# PICMX340F512H.net
KiCad netlist of a schematic drawn in Altium Designer
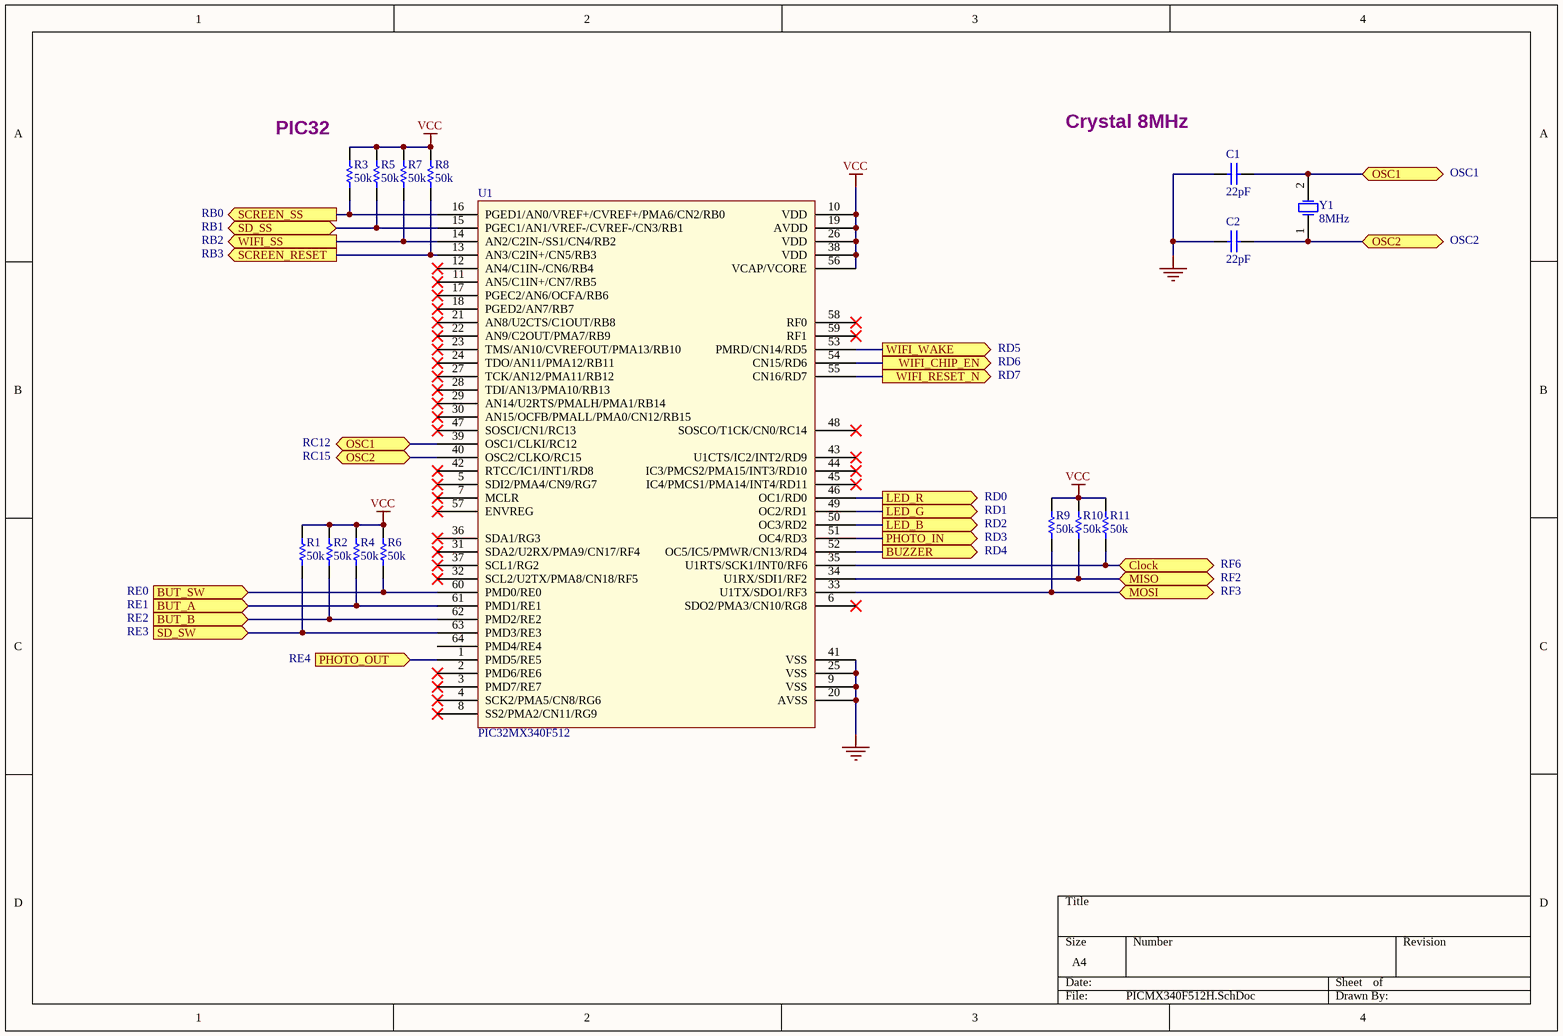
[diagram p0: PICMX340F512H.SchDoc]

(export (version "E")
  (design (tool "Eeschema 10.0.6"))
  (components
    (comp (ref "C1")
      (value "22pF")
      (footprint "CAPC1608X90N")
      (description "Capacitor")
      (libsource (lib "POP_lib") (part "Capacitor"))
    )
    (comp (ref "C2")
      (value "22pF")
      (footprint "CAPC1608X90N")
      (description "Capacitor")
      (libsource (lib "POP_lib") (part "Capacitor"))
    )
    (comp (ref "R1")
      (value "50k")
      (footprint "RESC1608X55N")
      (description "Resistor")
      (fields (field (name "PUBLISHER") "Altium Limited"))
      (libsource (lib "POP_lib") (part "Resistor"))
    )
    (comp (ref "R2")
      (value "50k")
      (footprint "RESC1608X55N")
      (description "Resistor")
      (fields (field (name "PUBLISHER") "Altium Limited"))
      (libsource (lib "POP_lib") (part "Resistor"))
    )
    (comp (ref "R3")
      (value "50k")
      (footprint "RESC1608X55N")
      (description "Resistor")
      (fields (field (name "PUBLISHER") "Altium Limited"))
      (libsource (lib "POP_lib") (part "Resistor"))
    )
    (comp (ref "R4")
      (value "50k")
      (footprint "RESC1608X55N")
      (description "Resistor")
      (fields (field (name "PUBLISHER") "Altium Limited"))
      (libsource (lib "POP_lib") (part "Resistor"))
    )
    (comp (ref "R5")
      (value "50k")
      (footprint "RESC1608X55N")
      (description "Resistor")
      (fields (field (name "PUBLISHER") "Altium Limited"))
      (libsource (lib "POP_lib") (part "Resistor"))
    )
    (comp (ref "R6")
      (value "50k")
      (footprint "RESC1608X55N")
      (description "Resistor")
      (fields (field (name "PUBLISHER") "Altium Limited"))
      (libsource (lib "POP_lib") (part "Resistor"))
    )
    (comp (ref "R7")
      (value "50k")
      (footprint "RESC1608X55N")
      (description "Resistor")
      (fields (field (name "PUBLISHER") "Altium Limited"))
      (libsource (lib "POP_lib") (part "Resistor"))
    )
    (comp (ref "R8")
      (value "50k")
      (footprint "RESC1608X55N")
      (description "Resistor")
      (fields (field (name "PUBLISHER") "Altium Limited"))
      (libsource (lib "POP_lib") (part "Resistor"))
    )
    (comp (ref "R9")
      (value "50k")
      (footprint "RESC1608X55N")
      (description "Resistor")
      (fields (field (name "PUBLISHER") "Altium Limited"))
      (libsource (lib "POP_lib") (part "Resistor"))
    )
    (comp (ref "R10")
      (value "50k")
      (footprint "RESC1608X55N")
      (description "Resistor")
      (fields (field (name "PUBLISHER") "Altium Limited"))
      (libsource (lib "POP_lib") (part "Resistor"))
    )
    (comp (ref "R11")
      (value "50k")
      (footprint "RESC1608X55N")
      (description "Resistor")
      (fields (field (name "PUBLISHER") "Altium Limited"))
      (libsource (lib "POP_lib") (part "Resistor"))
    )
    (comp (ref "U1")
      (value "PIC32MX340F512")
      (description "Protoboard_pic")
      (libsource (lib "POP_lib") (part "PIC32MX340F512H"))
    )
    (comp (ref "Y1")
      (value "8MHz")
      (footprint "XTAL139X50X45")
      (description "Crystal Oscillator")
      (libsource (lib "POP_lib") (part "Crystal"))
    )
  )
  (nets
    (net (code "1") (name "/BUT_A") (class "Default")
      (node (ref "R4") (pin "1") (pinfunction "1_1") (pintype "passive"))
      (node (ref "U1") (pin "61") (pinfunction "PMD1/RE1_61") (pintype "passive"))
    )
    (net (code "2") (name "/BUT_B") (class "Default")
      (node (ref "R2") (pin "1") (pinfunction "1_1") (pintype "passive"))
      (node (ref "U1") (pin "62") (pinfunction "PMD2/RE2_62") (pintype "passive"))
    )
    (net (code "3") (name "/BUT_SW") (class "Default")
      (node (ref "R6") (pin "1") (pinfunction "1_1") (pintype "passive"))
      (node (ref "U1") (pin "60") (pinfunction "PMD0/RE0_60") (pintype "passive"))
    )
    (net (code "4") (name "/BUZZER") (class "Default")
      (node (ref "U1") (pin "52") (pinfunction "OC5/IC5/PMWR/CN13/RD4_52") (pintype "passive"))
    )
    (net (code "5") (name "/Clock") (class "Default")
      (node (ref "R11") (pin "1") (pinfunction "1_1") (pintype "passive"))
      (node (ref "U1") (pin "35") (pinfunction "U1RTS/SCK1/INT0/RF6_35") (pintype "passive"))
    )
    (net (code "6") (name "/LED_B") (class "Default")
      (node (ref "U1") (pin "50") (pinfunction "OC3/RD2_50") (pintype "passive"))
    )
    (net (code "7") (name "/LED_G") (class "Default")
      (node (ref "U1") (pin "49") (pinfunction "OC2/RD1_49") (pintype "passive"))
    )
    (net (code "8") (name "/LED_R") (class "Default")
      (node (ref "U1") (pin "46") (pinfunction "OC1/RD0_46") (pintype "passive"))
    )
    (net (code "9") (name "/MISO") (class "Default")
      (node (ref "R10") (pin "1") (pinfunction "1_1") (pintype "passive"))
      (node (ref "U1") (pin "34") (pinfunction "U1RX/SDI1/RF2_34") (pintype "passive"))
    )
    (net (code "10") (name "/MOSI") (class "Default")
      (node (ref "R9") (pin "1") (pinfunction "1_1") (pintype "passive"))
      (node (ref "U1") (pin "33") (pinfunction "U1TX/SDO1/RF3_33") (pintype "passive"))
    )
    (net (code "11") (name "/OSC1") (class "Default")
      (node (ref "C1") (pin "1") (pinfunction "1_1") (pintype "passive"))
      (node (ref "U1") (pin "39") (pinfunction "OSC1/CLKI/RC12_39") (pintype "passive"))
      (node (ref "Y1") (pin "2") (pinfunction "OSC2_2") (pintype "passive"))
    )
    (net (code "12") (name "/OSC2") (class "Default")
      (node (ref "C2") (pin "1") (pinfunction "1_1") (pintype "passive"))
      (node (ref "U1") (pin "40") (pinfunction "OSC2/CLKO/RC15_40") (pintype "passive"))
      (node (ref "Y1") (pin "1") (pinfunction "OSC1_1") (pintype "passive"))
    )
    (net (code "13") (name "/PHOTO_IN") (class "Default")
      (node (ref "U1") (pin "51") (pinfunction "OC4/RD3_51") (pintype "passive"))
    )
    (net (code "14") (name "/PHOTO_OUT") (class "Default")
      (node (ref "U1") (pin "1") (pinfunction "PMD5/RE5_1") (pintype "passive"))
    )
    (net (code "15") (name "/SCREEN_RESET") (class "Default")
      (node (ref "R8") (pin "1") (pinfunction "1_1") (pintype "passive"))
      (node (ref "U1") (pin "13") (pinfunction "AN3/C2IN+/CN5/RB3_13") (pintype "passive"))
    )
    (net (code "16") (name "/SCREEN_SS") (class "Default")
      (node (ref "R3") (pin "1") (pinfunction "1_1") (pintype "passive"))
      (node (ref "U1") (pin "16") (pinfunction "PGED1/AN0/VREF+/CVREF+/PMA6/CN2/RB0_16") (pintype "passive"))
    )
    (net (code "17") (name "/SD_SS") (class "Default")
      (node (ref "R5") (pin "1") (pinfunction "1_1") (pintype "passive"))
      (node (ref "U1") (pin "15") (pinfunction "PGEC1/AN1/VREF-/CVREF-/CN3/RB1_15") (pintype "passive"))
    )
    (net (code "18") (name "/SD_SW") (class "Default")
      (node (ref "R1") (pin "1") (pinfunction "1_1") (pintype "passive"))
      (node (ref "U1") (pin "63") (pinfunction "PMD3/RE3_63") (pintype "passive"))
    )
    (net (code "19") (name "/WIFI_CHIP_EN") (class "Default")
      (node (ref "U1") (pin "54") (pinfunction "CN15/RD6_54") (pintype "passive"))
    )
    (net (code "20") (name "/WIFI_RESET_N") (class "Default")
      (node (ref "U1") (pin "55") (pinfunction "CN16/RD7_55") (pintype "passive"))
    )
    (net (code "21") (name "/WIFI_SS") (class "Default")
      (node (ref "R7") (pin "1") (pinfunction "1_1") (pintype "passive"))
      (node (ref "U1") (pin "14") (pinfunction "AN2/C2IN-/SS1/CN4/RB2_14") (pintype "passive"))
    )
    (net (code "22") (name "/WIFI_WAKE") (class "Default")
      (node (ref "U1") (pin "53") (pinfunction "PMRD/CN14/RD5_53") (pintype "passive"))
    )
    (net (code "23") (name "GND") (class "Default")
      (node (ref "C1") (pin "2") (pinfunction "2_2") (pintype "passive"))
      (node (ref "C2") (pin "2") (pinfunction "2_2") (pintype "passive"))
      (node (ref "U1") (pin "20") (pinfunction "AVSS_20") (pintype "passive"))
      (node (ref "U1") (pin "25") (pinfunction "VSS_25") (pintype "passive"))
      (node (ref "U1") (pin "41") (pinfunction "VSS_41") (pintype "passive"))
      (node (ref "U1") (pin "9") (pinfunction "VSS_9") (pintype "passive"))
    )
    (net (code "24") (name "VCC") (class "Default")
      (node (ref "R1") (pin "2") (pinfunction "2_2") (pintype "passive"))
      (node (ref "R10") (pin "2") (pinfunction "2_2") (pintype "passive"))
      (node (ref "R11") (pin "2") (pinfunction "2_2") (pintype "passive"))
      (node (ref "R2") (pin "2") (pinfunction "2_2") (pintype "passive"))
      (node (ref "R3") (pin "2") (pinfunction "2_2") (pintype "passive"))
      (node (ref "R4") (pin "2") (pinfunction "2_2") (pintype "passive"))
      (node (ref "R5") (pin "2") (pinfunction "2_2") (pintype "passive"))
      (node (ref "R6") (pin "2") (pinfunction "2_2") (pintype "passive"))
      (node (ref "R7") (pin "2") (pinfunction "2_2") (pintype "passive"))
      (node (ref "R8") (pin "2") (pinfunction "2_2") (pintype "passive"))
      (node (ref "R9") (pin "2") (pinfunction "2_2") (pintype "passive"))
      (node (ref "U1") (pin "10") (pinfunction "VDD_10") (pintype "passive"))
      (node (ref "U1") (pin "19") (pinfunction "AVDD_19") (pintype "passive"))
      (node (ref "U1") (pin "26") (pinfunction "VDD_26") (pintype "passive"))
      (node (ref "U1") (pin "38") (pinfunction "VDD_38") (pintype "passive"))
      (node (ref "U1") (pin "56") (pinfunction "VCAP/VCORE_56") (pintype "passive"))
    )
    (net (code "25") (name "unconnected-(U1-AN4{slash}C1IN-{slash}CN6{slash}RB4-Pad12)") (class "Default")
      (node (ref "U1") (pin "12") (pinfunction "AN4/C1IN-/CN6/RB4_12") (pintype "passive+no_connect"))
    )
    (net (code "26") (name "unconnected-(U1-AN5{slash}C1IN+{slash}CN7{slash}RB5-Pad11)") (class "Default")
      (node (ref "U1") (pin "11") (pinfunction "AN5/C1IN+/CN7/RB5_11") (pintype "passive+no_connect"))
    )
    (net (code "27") (name "unconnected-(U1-AN8{slash}U2CTS{slash}C1OUT{slash}RB8-Pad21)") (class "Default")
      (node (ref "U1") (pin "21") (pinfunction "AN8/U2CTS/C1OUT/RB8_21") (pintype "passive+no_connect"))
    )
    (net (code "28") (name "unconnected-(U1-AN9{slash}C2OUT{slash}PMA7{slash}RB9-Pad22)") (class "Default")
      (node (ref "U1") (pin "22") (pinfunction "AN9/C2OUT/PMA7/RB9_22") (pintype "passive+no_connect"))
    )
    (net (code "29") (name "unconnected-(U1-AN14{slash}U2RTS{slash}PMALH{slash}PMA1{slash}RB14-Pad29)") (class "Default")
      (node (ref "U1") (pin "29") (pinfunction "AN14/U2RTS/PMALH/PMA1/RB14_29") (pintype "passive+no_connect"))
    )
    (net (code "30") (name "unconnected-(U1-AN15{slash}OCFB{slash}PMALL{slash}PMA0{slash}CN12{slash}RB15-Pad30)") (class "Default")
      (node (ref "U1") (pin "30") (pinfunction "AN15/OCFB/PMALL/PMA0/CN12/RB15_30") (pintype "passive+no_connect"))
    )
    (net (code "31") (name "unconnected-(U1-ENVREG-Pad57)") (class "Default")
      (node (ref "U1") (pin "57") (pinfunction "ENVREG_57") (pintype "passive+no_connect"))
    )
    (net (code "32") (name "unconnected-(U1-IC3{slash}PMCS2{slash}PMA15{slash}INT3{slash}RD10-Pad44)") (class "Default")
      (node (ref "U1") (pin "44") (pinfunction "IC3/PMCS2/PMA15/INT3/RD10_44") (pintype "passive+no_connect"))
    )
    (net (code "33") (name "unconnected-(U1-IC4{slash}PMCS1{slash}PMA14{slash}INT4{slash}RD11-Pad45)") (class "Default")
      (node (ref "U1") (pin "45") (pinfunction "IC4/PMCS1/PMA14/INT4/RD11_45") (pintype "passive+no_connect"))
    )
    (net (code "34") (name "unconnected-(U1-MCLR-Pad7)") (class "Default")
      (node (ref "U1") (pin "7") (pinfunction "MCLR_7") (pintype "passive+no_connect"))
    )
    (net (code "35") (name "unconnected-(U1-PGEC2{slash}AN6{slash}OCFA{slash}RB6-Pad17)") (class "Default")
      (node (ref "U1") (pin "17") (pinfunction "PGEC2/AN6/OCFA/RB6_17") (pintype "passive+no_connect"))
    )
    (net (code "36") (name "unconnected-(U1-PGED2{slash}AN7{slash}RB7-Pad18)") (class "Default")
      (node (ref "U1") (pin "18") (pinfunction "PGED2/AN7/RB7_18") (pintype "passive+no_connect"))
    )
    (net (code "37") (name "unconnected-(U1-PMD4{slash}RE4-Pad64)") (class "Default")
      (node (ref "U1") (pin "64") (pinfunction "PMD4/RE4_64") (pintype "passive"))
    )
    (net (code "38") (name "unconnected-(U1-PMD6{slash}RE6-Pad2)") (class "Default")
      (node (ref "U1") (pin "2") (pinfunction "PMD6/RE6_2") (pintype "passive+no_connect"))
    )
    (net (code "39") (name "unconnected-(U1-PMD7{slash}RE7-Pad3)") (class "Default")
      (node (ref "U1") (pin "3") (pinfunction "PMD7/RE7_3") (pintype "passive+no_connect"))
    )
    (net (code "40") (name "unconnected-(U1-RF0-Pad58)") (class "Default")
      (node (ref "U1") (pin "58") (pinfunction "RF0_58") (pintype "passive+no_connect"))
    )
    (net (code "41") (name "unconnected-(U1-RF1-Pad59)") (class "Default")
      (node (ref "U1") (pin "59") (pinfunction "RF1_59") (pintype "passive+no_connect"))
    )
    (net (code "42") (name "unconnected-(U1-RTCC{slash}IC1{slash}INT1{slash}RD8-Pad42)") (class "Default")
      (node (ref "U1") (pin "42") (pinfunction "RTCC/IC1/INT1/RD8_42") (pintype "passive+no_connect"))
    )
    (net (code "43") (name "unconnected-(U1-SCK2{slash}PMA5{slash}CN8{slash}RG6-Pad4)") (class "Default")
      (node (ref "U1") (pin "4") (pinfunction "SCK2/PMA5/CN8/RG6_4") (pintype "passive+no_connect"))
    )
    (net (code "44") (name "unconnected-(U1-SCL1{slash}RG2-Pad37)") (class "Default")
      (node (ref "U1") (pin "37") (pinfunction "SCL1/RG2_37") (pintype "passive+no_connect"))
    )
    (net (code "45") (name "unconnected-(U1-SCL2{slash}U2TX{slash}PMA8{slash}CN18{slash}RF5-Pad32)") (class "Default")
      (node (ref "U1") (pin "32") (pinfunction "SCL2/U2TX/PMA8/CN18/RF5_32") (pintype "passive+no_connect"))
    )
    (net (code "46") (name "unconnected-(U1-SDA1{slash}RG3-Pad36)") (class "Default")
      (node (ref "U1") (pin "36") (pinfunction "SDA1/RG3_36") (pintype "passive+no_connect"))
    )
    (net (code "47") (name "unconnected-(U1-SDA2{slash}U2RX{slash}PMA9{slash}CN17{slash}RF4-Pad31)") (class "Default")
      (node (ref "U1") (pin "31") (pinfunction "SDA2/U2RX/PMA9/CN17/RF4_31") (pintype "passive+no_connect"))
    )
    (net (code "48") (name "unconnected-(U1-SDI2{slash}PMA4{slash}CN9{slash}RG7-Pad5)") (class "Default")
      (node (ref "U1") (pin "5") (pinfunction "SDI2/PMA4/CN9/RG7_5") (pintype "passive+no_connect"))
    )
    (net (code "49") (name "unconnected-(U1-SDO2{slash}PMA3{slash}CN10{slash}RG8-Pad6)") (class "Default")
      (node (ref "U1") (pin "6") (pinfunction "SDO2/PMA3/CN10/RG8_6") (pintype "passive+no_connect"))
    )
    (net (code "50") (name "unconnected-(U1-SOSCI{slash}CN1{slash}RC13-Pad47)") (class "Default")
      (node (ref "U1") (pin "47") (pinfunction "SOSCI/CN1/RC13_47") (pintype "passive+no_connect"))
    )
    (net (code "51") (name "unconnected-(U1-SOSCO{slash}T1CK{slash}CN0{slash}RC14-Pad48)") (class "Default")
      (node (ref "U1") (pin "48") (pinfunction "SOSCO/T1CK/CN0/RC14_48") (pintype "passive+no_connect"))
    )
    (net (code "52") (name "unconnected-(U1-SS2{slash}PMA2{slash}CN11{slash}RG9-Pad8)") (class "Default")
      (node (ref "U1") (pin "8") (pinfunction "SS2/PMA2/CN11/RG9_8") (pintype "passive+no_connect"))
    )
    (net (code "53") (name "unconnected-(U1-TCK{slash}AN12{slash}PMA11{slash}RB12-Pad27)") (class "Default")
      (node (ref "U1") (pin "27") (pinfunction "TCK/AN12/PMA11/RB12_27") (pintype "passive+no_connect"))
    )
    (net (code "54") (name "unconnected-(U1-TDI{slash}AN13{slash}PMA10{slash}RB13-Pad28)") (class "Default")
      (node (ref "U1") (pin "28") (pinfunction "TDI/AN13/PMA10/RB13_28") (pintype "passive+no_connect"))
    )
    (net (code "55") (name "unconnected-(U1-TDO{slash}AN11{slash}PMA12{slash}RB11-Pad24)") (class "Default")
      (node (ref "U1") (pin "24") (pinfunction "TDO/AN11/PMA12/RB11_24") (pintype "passive+no_connect"))
    )
    (net (code "56") (name "unconnected-(U1-TMS{slash}AN10{slash}CVREFOUT{slash}PMA13{slash}RB10-Pad23)") (class "Default")
      (node (ref "U1") (pin "23") (pinfunction "TMS/AN10/CVREFOUT/PMA13/RB10_23") (pintype "passive+no_connect"))
    )
    (net (code "57") (name "unconnected-(U1-U1CTS{slash}IC2{slash}INT2{slash}RD9-Pad43)") (class "Default")
      (node (ref "U1") (pin "43") (pinfunction "U1CTS/IC2/INT2/RD9_43") (pintype "passive+no_connect"))
    )
  )
)
